# Sheet1.net
KiCad netlist of a schematic drawn in Altium Designer
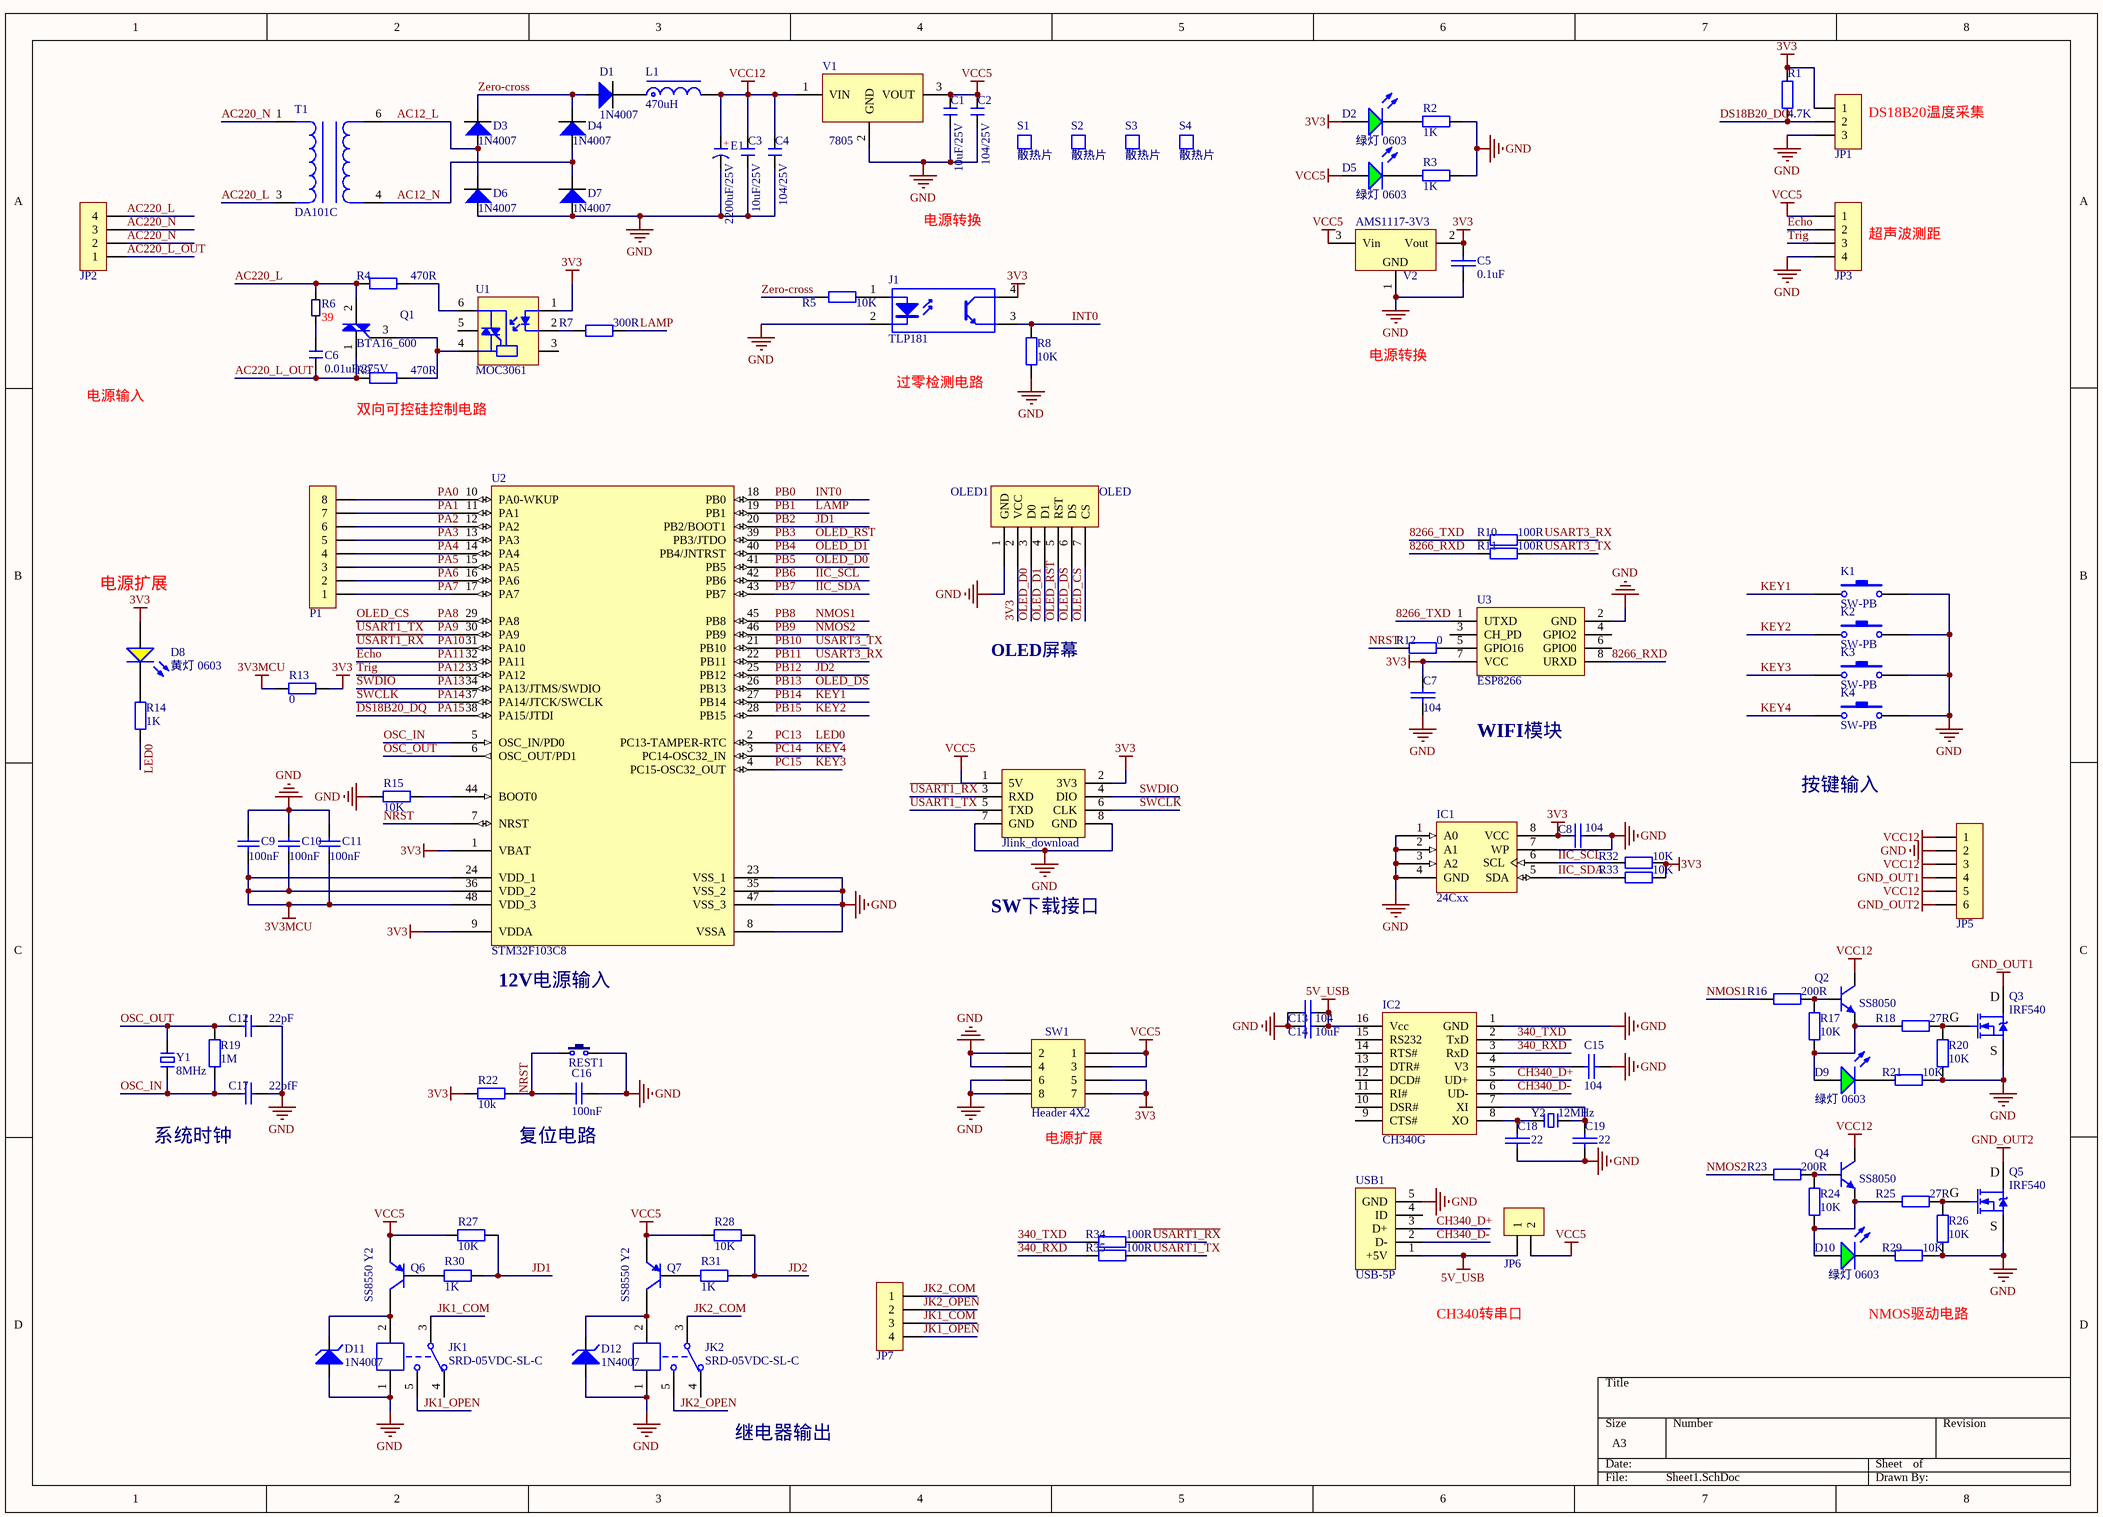
[diagram p0: Sheet1.SchDoc]

(export (version "E")
  (design (tool "Eeschema 10.0.6"))
  (components
    (comp (ref "*1")
      (value "Jlink_download")
      (footprint "HDR2.54-M-LI-2x4P")
      (description "Jlink下载器")
      (libsource (lib "15.1 - 未分类器件") (part "Jlink_下载器"))
    )
    (comp (ref "C1")
      (value "10uF/25V")
      (footprint "LC-0805_C")
      (description "无极性贴片电容")
      (fields (field (name "版权归属") "源创客"))
      (libsource (lib "3.1   - 电阻-电容-电感") (part "C"))
    )
    (comp (ref "C2")
      (value "104/25V")
      (footprint "LC-0603_C")
      (description "无极性贴片电容")
      (fields (field (name "版权归属") "源创客"))
      (libsource (lib "3.1   - 电阻-电容-电感") (part "C"))
    )
    (comp (ref "C3")
      (value "10uF/25V")
      (footprint "LC-0805_C")
      (description "无极性贴片电容")
      (fields (field (name "版权归属") "源创客"))
      (libsource (lib "3.1   - 电阻-电容-电感") (part "C"))
    )
    (comp (ref "C4")
      (value "104/25V")
      (footprint "LC-0603_C")
      (description "无极性贴片电容")
      (fields (field (name "版权归属") "源创客"))
      (libsource (lib "3.1   - 电阻-电容-电感") (part "C"))
    )
    (comp (ref "C5")
      (value "0.1uF")
      (footprint "LC-0603_C")
      (description "Capacitor 0805")
      (libsource (lib "CD's_LIB_2018") (part "0805C"))
    )
    (comp (ref "C6")
      (value "0.01uF/275V")
      (footprint "CBB 10*12*8")
      (description "CBB电容")
      (fields (field (name "版权归属") "源创客"))
      (libsource (lib "3.1   - 电阻-电容-电感") (part "C-CBB"))
    )
    (comp (ref "C7")
      (value "104")
      (footprint "LC-0603_C")
      (description "Capacitor 0805")
      (libsource (lib "CD's_LIB_2018") (part "0805C"))
    )
    (comp (ref "C8")
      (value "104")
      (footprint "LC-0603_C")
      (description "Capacitor 0805")
      (libsource (lib "CD's_LIB_2018") (part "0805C"))
    )
    (comp (ref "C9")
      (value "100nF")
      (footprint "LC-0603_C")
      (description "无极性电容")
      (fields (field (name "PUBLISHER") "Altium Limited"))
      (libsource (lib "liu_2016") (part "Cap"))
    )
    (comp (ref "C10")
      (value "100nF")
      (footprint "LC-0603_C")
      (description "无极性电容")
      (fields (field (name "PUBLISHER") "Altium Limited"))
      (libsource (lib "liu_2016") (part "Cap"))
    )
    (comp (ref "C11")
      (value "100nF")
      (footprint "LC-0603_C")
      (description "无极性电容")
      (fields (field (name "PUBLISHER") "Altium Limited"))
      (libsource (lib "liu_2016") (part "Cap"))
    )
    (comp (ref "C12")
      (value "22pF")
      (footprint "LC-0603_C")
      (description "无极性电容")
      (fields (field (name "PUBLISHER") "Altium Limited"))
      (libsource (lib "liu_2016") (part "Cap"))
    )
    (comp (ref "C13")
      (value "104")
      (footprint "LC-0603_C")
      (description "Capacitor 0805")
      (libsource (lib "CD's_LIB_2018") (part "0805C"))
    )
    (comp (ref "C14")
      (value "10uF")
      (footprint "LC-0805_C")
      (description "Capacitor 0805")
      (libsource (lib "CD's_LIB_2018") (part "0805C"))
    )
    (comp (ref "C15")
      (value "104")
      (footprint "LC-0603_C")
      (description "Capacitor 0805")
      (libsource (lib "CD's_LIB_2018") (part "0805C"))
    )
    (comp (ref "C16")
      (value "100nF")
      (footprint "LC-0603_C")
      (description "无极性电容")
      (fields (field (name "PUBLISHER") "Altium Limited"))
      (libsource (lib "liu_2016") (part "Cap"))
    )
    (comp (ref "C17")
      (value "22pfF")
      (footprint "LC-0603_C")
      (description "无极性电容")
      (fields (field (name "PUBLISHER") "Altium Limited"))
      (libsource (lib "liu_2016") (part "Cap"))
    )
    (comp (ref "C18")
      (value "22")
      (footprint "LC-0603_C")
      (description "Capacitor 0805")
      (libsource (lib "CD's_LIB_2018") (part "0805C"))
    )
    (comp (ref "C19")
      (value "22")
      (footprint "LC-0603_C")
      (description "Capacitor 0805")
      (libsource (lib "CD's_LIB_2018") (part "0805C"))
    )
    (comp (ref "D1") (value "1N4007") (footprint "DO-41") (libsource (lib "SWUST_PanPan") (part "1N4007")))
    (comp (ref "D2")
      (value "绿灯 0603")
      (footprint "LC-0603_LED_S1")
      (description "发光二极管")
      (libsource (lib "Miscellaneous Devices LC") (part "0603 绿灯"))
    )
    (comp (ref "D3") (value "1N4007") (footprint "DO-41") (libsource (lib "SWUST_PanPan") (part "1N4007")))
    (comp (ref "D4") (value "1N4007") (footprint "DO-41") (libsource (lib "SWUST_PanPan") (part "1N4007")))
    (comp (ref "D5")
      (value "绿灯 0603")
      (footprint "LC-0603_LED_S1")
      (description "发光二极管")
      (libsource (lib "Miscellaneous Devices LC") (part "0603 绿灯"))
    )
    (comp (ref "D6") (value "1N4007") (footprint "DO-41") (libsource (lib "SWUST_PanPan") (part "1N4007")))
    (comp (ref "D7") (value "1N4007") (footprint "DO-41") (libsource (lib "SWUST_PanPan") (part "1N4007")))
    (comp (ref "D8")
      (value "黄灯 0603")
      (footprint "LC-0603_LED_S1")
      (description "发光二极管")
      (libsource (lib "Miscellaneous Devices LC") (part "0603 黄灯"))
    )
    (comp (ref "D9")
      (value "绿灯 0603")
      (footprint "LC-0603_LED_S1")
      (description "发光二极管")
      (libsource (lib "Miscellaneous Devices LC") (part "0603 绿灯"))
    )
    (comp (ref "D10")
      (value "绿灯 0603")
      (footprint "LC-0603_LED_S1")
      (description "发光二极管")
      (libsource (lib "Miscellaneous Devices LC") (part "0603 绿灯"))
    )
    (comp (ref "D11")
      (value "1N4007")
      (footprint "D1812")
      (description "Zener Diode")
      (libsource (lib "CD's_LIB_2018") (part "1N4007"))
    )
    (comp (ref "D12")
      (value "1N4007")
      (footprint "D1812")
      (description "Zener Diode")
      (libsource (lib "CD's_LIB_2018") (part "1N4007"))
    )
    (comp (ref "E1")
      (value "2200uF/25V")
      (footprint "CAP 7.5*16*31.5 - BK")
      (description "直插电解电容")
      (fields (field (name "版权归属") "源创客"))
      (libsource (lib "3.1   - 电阻-电容-电感") (part "C-CAP"))
    )
    (comp (ref "IC1")
      (value "24Cxx")
      (footprint "SOP8_M")
      (description "外置EEPROM")
      (fields (field (name "版权归属") "源创客"))
      (libsource (lib "1.1   - IC芯片") (part "24Cxx"))
    )
    (comp (ref "IC2")
      (value "CH340G")
      (footprint "SOP16_M")
      (description "串口转USB")
      (fields (field (name "版权归属") "源创客"))
      (libsource (lib "1.1   - IC芯片") (part "CH340G"))
    )
    (comp (ref "J1")
      (value "TLP181")
      (footprint "SOP4-W2.54_M")
      (description "光耦")
      (fields (field (name "版权归属") "源创客"))
      (libsource (lib "11.1 - 传感元件") (part "TLP181"))
    )
    (comp (ref "JK1")
      (value "SRD-05VDC-SL-C")
      (footprint "SRD-C_B")
      (description "5V一组转换")
      (fields (field (name "版权归属") "源创客"))
      (libsource (lib "7.1   - 继电器") (part "SRD-05VDC-SL-C"))
    )
    (comp (ref "JK2")
      (value "SRD-05VDC-SL-C")
      (footprint "SRD-C_B")
      (description "5V一组转换")
      (fields (field (name "版权归属") "源创客"))
      (libsource (lib "7.1   - 继电器") (part "SRD-05VDC-SL-C"))
    )
    (comp (ref "JP1")
      (value "HDR-1X3")
      (footprint "XH2.54-WI-3P")
      (description "3P接插件")
      (fields (field (name "版权归属") "源创客"))
      (libsource (lib "4.5   - 接插件-脚距2.54") (part "Header 3"))
    )
    (comp (ref "JP2")
      (value "HDR-1X4")
      (footprint "KF128-5.08-4P")
      (description "4P接插件")
      (fields (field (name "版权归属") "源创客"))
      (libsource (lib "4.10 - 接插件-脚距5.08") (part "Header 4"))
    )
    (comp (ref "JP3")
      (value "HDR-1X4")
      (footprint "XH2.54-WI-4P")
      (description "4P接插件")
      (fields (field (name "版权归属") "源创客"))
      (libsource (lib "4.5   - 接插件-脚距2.54") (part "Header 4"))
    )
    (comp (ref "JP5")
      (value "HDR-1X6")
      (footprint "KF128-5.08-6P")
      (description "6P接插件")
      (fields (field (name "版权归属") "源创客"))
      (libsource (lib "4.10 - 接插件-脚距5.08") (part "Header 6"))
    )
    (comp (ref "JP6")
      (value "HDR-1X2")
      (footprint "HDR2.54-LI-2P")
      (description "2P接插件")
      (fields (field (name "版权归属") "源创客"))
      (libsource (lib "4.5   - 接插件-脚距2.54") (part "Header 2"))
    )
    (comp (ref "JP7")
      (value "HDR-1X4")
      (footprint "KF128-5.08-4P")
      (description "4P接插件")
      (fields (field (name "版权归属") "源创客"))
      (libsource (lib "") (part "Header 4_1"))
    )
    (comp (ref "K1")
      (value "SW-PB")
      (footprint "TSW DIP-6*6*5")
      (description "Switch")
      (fields (field (name "PUBLISHER") "Altium Limited"))
      (libsource (lib "PCB_Project") (part "SW-PB"))
    )
    (comp (ref "K2")
      (value "SW-PB")
      (footprint "TSW DIP-6*6*5")
      (description "Switch")
      (fields (field (name "PUBLISHER") "Altium Limited"))
      (libsource (lib "PCB_Project") (part "SW-PB"))
    )
    (comp (ref "K3")
      (value "SW-PB")
      (footprint "TSW DIP-6*6*5")
      (description "Switch")
      (fields (field (name "PUBLISHER") "Altium Limited"))
      (libsource (lib "PCB_Project") (part "SW-PB"))
    )
    (comp (ref "K4")
      (value "SW-PB")
      (footprint "TSW DIP-6*6*5")
      (description "Switch")
      (fields (field (name "PUBLISHER") "Altium Limited"))
      (libsource (lib "PCB_Project") (part "SW-PB"))
    )
    (comp (ref "L1")
      (value "470uH")
      (footprint "LMR135")
      (description "功率磁环电感")
      (fields (field (name "版权归属") "源创客"))
      (libsource (lib "3.1   - 电阻-电容-电感") (part "L-MR"))
    )
    (comp (ref "OLED1")
      (value "OLED")
      (footprint "OLED_096")
      (description "OLED屏幕")
      (libsource (lib "liu_2016") (part "OLED_SPI"))
    )
    (comp (ref "P1")
      (value "HDR-1X8")
      (footprint "HDR2.54-LI-8P")
      (description "8P接插件")
      (fields (field (name "版权归属") "源创客"))
      (libsource (lib "4.5   - 接插件-脚距2.54") (part "Header 8"))
    )
    (comp (ref "Q1")
      (value "BTA16_600")
      (footprint "TO220A")
      (description "双向可控硅")
      (fields (field (name "版权归属") "源创客"))
      (libsource (lib "6.1   - 场效应管-可控硅") (part "BTA12_600"))
    )
    (comp (ref "Q2")
      (value "SS8050")
      (footprint "SOT23-3L")
      (description "高频放大-NPN型")
      (fields (field (name "版权归属") "源创客"))
      (libsource (lib "6.2   - 三极管") (part "8050-SMD"))
    )
    (comp (ref "Q3")
      (value "IRF540")
      (footprint "TO220A")
      (description "N沟场效应管")
      (fields (field (name "版权归属") "源创客"))
      (libsource (lib "6.1   - 场效应管-可控硅") (part "IRF840"))
    )
    (comp (ref "Q4")
      (value "SS8050")
      (footprint "SOT23-3L")
      (description "高频放大-NPN型")
      (fields (field (name "版权归属") "源创客"))
      (libsource (lib "6.2   - 三极管") (part "8050-SMD"))
    )
    (comp (ref "Q5")
      (value "IRF540")
      (footprint "TO220A")
      (description "N沟场效应管")
      (fields (field (name "版权归属") "源创客"))
      (libsource (lib "6.1   - 场效应管-可控硅") (part "IRF840"))
    )
    (comp (ref "Q6")
      (value "SS8550 Y2")
      (footprint "LC-SOT-23(SOT-23-3)")
      (description "三极管")
      (libsource (lib "Miscellaneous Devices LC") (part "SOT-23 SS8550 Y2"))
    )
    (comp (ref "Q7")
      (value "SS8550 Y2")
      (footprint "LC-SOT-23(SOT-23-3)")
      (description "三极管")
      (libsource (lib "Miscellaneous Devices LC") (part "SOT-23 SS8550 Y2"))
    )
    (comp (ref "R1")
      (value "4.7K")
      (footprint "LC-0603_R")
      (description "贴片电阻")
      (fields (field (name "PUBLISHER") "Altium Limited"))
      (libsource (lib "") (part "Res1_1"))
    )
    (comp (ref "R2")
      (value "1K")
      (footprint "LC-0603_R")
      (description "贴片电阻")
      (libsource (lib "Miscellaneous Devices LC") (part "0603 1.1KΩ (1101) 1%"))
    )
    (comp (ref "R3")
      (value "1K")
      (footprint "LC-0603_R")
      (description "贴片电阻")
      (libsource (lib "Miscellaneous Devices LC") (part "0603 1.1KΩ (1101) 1%"))
    )
    (comp (ref "R4")
      (value "470R")
      (footprint "RS 1/2W")
      (description "直插色环电阻")
      (fields (field (name "版权归属") "源创客"))
      (libsource (lib "3.1   - 电阻-电容-电感") (part "R-CRR"))
    )
    (comp (ref "R5")
      (value "10K")
      (footprint "LC-0603_R")
      (description "贴片电阻")
      (fields (field (name "PUBLISHER") "Altium Limited"))
      (libsource (lib "") (part "Res1_2"))
    )
    (comp (ref "R6") (value "39") (footprint "RS 2W") (libsource (lib "SWUST_PanPan") (part "RES-0603")))
    (comp (ref "R7")
      (value "300R")
      (footprint "LC-0603_R")
      (description "贴片电阻")
      (fields (field (name "PUBLISHER") "Altium Limited"))
      (libsource (lib "") (part "Res1_2"))
    )
    (comp (ref "R8")
      (value "10K")
      (footprint "LC-0603_R")
      (description "贴片电阻")
      (fields (field (name "PUBLISHER") "Altium Limited"))
      (libsource (lib "") (part "Res1_3"))
    )
    (comp (ref "R9")
      (value "470R")
      (footprint "RS 1/2W")
      (description "直插色环电阻")
      (fields (field (name "版权归属") "源创客"))
      (libsource (lib "3.1   - 电阻-电容-电感") (part "R-CRR"))
    )
    (comp (ref "R10")
      (value "100R")
      (footprint "LC-0603_R")
      (description "贴片电阻")
      (fields (field (name "PUBLISHER") "Altium Limited"))
      (libsource (lib "liu_2016") (part "Res1"))
    )
    (comp (ref "R11")
      (value "100R")
      (footprint "LC-0603_R")
      (description "贴片电阻")
      (fields (field (name "PUBLISHER") "Altium Limited"))
      (libsource (lib "liu_2016") (part "Res1"))
    )
    (comp (ref "R12")
      (value "0")
      (footprint "LC-0603_R")
      (description "贴片电阻")
      (fields (field (name "PUBLISHER") "Altium Limited"))
      (libsource (lib "liu_2016") (part "Res1"))
    )
    (comp (ref "R13")
      (value "0")
      (footprint "LC-0603_R")
      (description "贴片电阻")
      (fields (field (name "PUBLISHER") "Altium Limited"))
      (libsource (lib "liu_2016") (part "Res1"))
    )
    (comp (ref "R14")
      (value "1K")
      (footprint "LC-0603_R")
      (description "贴片电阻")
      (fields (field (name "PUBLISHER") "Altium Limited"))
      (libsource (lib "") (part "Res1_1"))
    )
    (comp (ref "R15")
      (value "10K")
      (footprint "LC-0603_R")
      (description "贴片电阻")
      (fields (field (name "PUBLISHER") "Altium Limited"))
      (libsource (lib "liu_2016") (part "Res1"))
    )
    (comp (ref "R16")
      (value "200R")
      (footprint "LC-0603_R")
      (description "贴片电阻")
      (fields (field (name "PUBLISHER") "Altium Limited"))
      (libsource (lib "") (part "Res1_1"))
    )
    (comp (ref "R17")
      (value "10K")
      (footprint "LC-0603_R")
      (description "贴片电阻")
      (fields (field (name "PUBLISHER") "Altium Limited"))
      (libsource (lib "毕业设计") (part "Res1"))
    )
    (comp (ref "R18")
      (value "27R")
      (footprint "LC-0603_R")
      (description "贴片电阻")
      (fields (field (name "PUBLISHER") "Altium Limited"))
      (libsource (lib "") (part "Res1_1"))
    )
    (comp (ref "R19")
      (value "1M")
      (footprint "LC-0603_R")
      (description "贴片电阻")
      (fields (field (name "PUBLISHER") "Altium Limited"))
      (libsource (lib "") (part "Res1_2"))
    )
    (comp (ref "R20")
      (value "10K")
      (footprint "LC-0603_R")
      (description "贴片电阻")
      (fields (field (name "PUBLISHER") "Altium Limited"))
      (libsource (lib "毕业设计") (part "Res1"))
    )
    (comp (ref "R21")
      (value "10K")
      (footprint "LC-0603_R")
      (description "贴片电阻")
      (libsource (lib "Miscellaneous Devices LC") (part "0603 1.1KΩ (1101) 1%"))
    )
    (comp (ref "R22")
      (value "10k")
      (footprint "LC-0603_R")
      (description "贴片电阻")
      (fields (field (name "PUBLISHER") "Altium Limited"))
      (libsource (lib "") (part "Res1_3"))
    )
    (comp (ref "R23")
      (value "200R")
      (footprint "LC-0603_R")
      (description "贴片电阻")
      (fields (field (name "PUBLISHER") "Altium Limited"))
      (libsource (lib "") (part "Res1_1"))
    )
    (comp (ref "R24")
      (value "10K")
      (footprint "LC-0603_R")
      (description "贴片电阻")
      (fields (field (name "PUBLISHER") "Altium Limited"))
      (libsource (lib "毕业设计") (part "Res1"))
    )
    (comp (ref "R25")
      (value "27R")
      (footprint "LC-0603_R")
      (description "贴片电阻")
      (fields (field (name "PUBLISHER") "Altium Limited"))
      (libsource (lib "") (part "Res1_1"))
    )
    (comp (ref "R26")
      (value "10K")
      (footprint "LC-0603_R")
      (description "贴片电阻")
      (fields (field (name "PUBLISHER") "Altium Limited"))
      (libsource (lib "毕业设计") (part "Res1"))
    )
    (comp (ref "R27")
      (value "10K")
      (footprint "LC-0603_R")
      (description "贴片电阻")
      (libsource (lib "Miscellaneous Devices LC") (part "0603 1.1KΩ (1101) 1%"))
    )
    (comp (ref "R28")
      (value "10K")
      (footprint "LC-0603_R")
      (description "贴片电阻")
      (libsource (lib "Miscellaneous Devices LC") (part "0603 1.1KΩ (1101) 1%"))
    )
    (comp (ref "R29")
      (value "10K")
      (footprint "LC-0603_R")
      (description "贴片电阻")
      (libsource (lib "Miscellaneous Devices LC") (part "0603 1.1KΩ (1101) 1%"))
    )
    (comp (ref "R30")
      (value "1K")
      (footprint "LC-0603_R")
      (description "贴片电阻")
      (libsource (lib "Miscellaneous Devices LC") (part "0603 1.1KΩ (1101) 1%"))
    )
    (comp (ref "R31")
      (value "1K")
      (footprint "LC-0603_R")
      (description "贴片电阻")
      (libsource (lib "Miscellaneous Devices LC") (part "0603 1.1KΩ (1101) 1%"))
    )
    (comp (ref "R32")
      (value "10K")
      (footprint "LC-0603_R")
      (description "贴片电阻")
      (libsource (lib "Miscellaneous Devices LC") (part "0603 1.1KΩ (1101) 1%"))
    )
    (comp (ref "R33")
      (value "10K")
      (footprint "LC-0603_R")
      (description "贴片电阻")
      (libsource (lib "Miscellaneous Devices LC") (part "0603 1.1KΩ (1101) 1%"))
    )
    (comp (ref "R34")
      (value "100R")
      (footprint "LC-0603_R")
      (description "贴片电阻")
      (fields (field (name "PUBLISHER") "Altium Limited"))
      (libsource (lib "liu_2016") (part "Res1"))
    )
    (comp (ref "R35")
      (value "100R")
      (footprint "LC-0603_R")
      (description "贴片电阻")
      (fields (field (name "PUBLISHER") "Altium Limited"))
      (libsource (lib "liu_2016") (part "Res1"))
    )
    (comp (ref "REST1")
      (value "3x6x5")
      (footprint "TSW SMD-3*6*2.5")
      (description "3x6轻触开关")
      (fields (field (name "版权归属") "源创客"))
      (libsource (lib "5.1   - 按键-开关") (part "TSW 3x6"))
    )
    (comp (ref "S1")
      (value "散热片")
      (footprint "SRP10-15-21-P")
      (fields (field (name "版权归属") "源创客"))
      (libsource (lib "15.1 - 未分类器件") (part "S1"))
    )
    (comp (ref "S2")
      (value "散热片")
      (footprint "SRP10-15-21-P")
      (fields (field (name "版权归属") "源创客"))
      (libsource (lib "15.1 - 未分类器件") (part "S1"))
    )
    (comp (ref "S3")
      (value "散热片")
      (footprint "SRP10-15-21-P")
      (fields (field (name "版权归属") "源创客"))
      (libsource (lib "15.1 - 未分类器件") (part "S1"))
    )
    (comp (ref "S4")
      (value "散热片")
      (footprint "SRP10-15-21-P")
      (fields (field (name "版权归属") "源创客"))
      (libsource (lib "15.1 - 未分类器件") (part "S1"))
    )
    (comp (ref "SW1")
      (value "Header 4X2")
      (footprint "HDR2.54-LI-2x4P")
      (description "Header, 4-Pin, Dual row")
      (fields (field (name "PUBLISHER") "Altium Limited"))
      (libsource (lib "Sparks") (part "Header 4X2"))
    )
    (comp (ref "T1")
      (value "DA101C")
      (footprint "Transformer_28mm")
      (description "数字隔离变压器")
      (fields (field (name "版权归属") "源创客"))
      (libsource (lib "12.1 - 变压器") (part "DA10XC"))
    )
    (comp (ref "U1")
      (value "MOC3061")
      (footprint "DIP6-300")
      (description "零点触发光可控硅")
      (fields (field (name "版权归属") "源创客"))
      (libsource (lib "6.1   - 场效应管-可控硅") (part "MOC3061"))
    )
    (comp (ref "U2")
      (value "STM32F103C8")
      (footprint "LQFP48 7X7_M")
      (description "Flaah:64/RAM:20/IO:36")
      (fields (field (name "版权归属") "源创客"))
      (libsource (lib "2.1   - STM32系列单片机") (part "STM32F103C8"))
    )
    (comp (ref "U3")
      (value "ESP8266")
      (footprint "2*4HEADER")
      (description "WIFI通信模块")
      (libsource (lib "13.1 - 模块") (part "ESP8266"))
    )
    (comp (ref "USB1")
      (value "USB-5P")
      (footprint "USB-MICRO_A")
      (description "微型USB母座")
      (fields (field (name "版权归属") "源创客"))
      (libsource (lib "4.1   - 接口类") (part "USB-5P"))
    )
    (comp (ref "V1")
      (value "7805")
      (footprint "TO220A")
      (description "线性稳压芯片")
      (fields (field (name "版权归属") "源创客"))
      (libsource (lib "1.3   - 电源类芯片") (part "78xx"))
    )
    (comp (ref "V2")
      (value "AMS1117-3V3")
      (footprint "SOT223_N")
      (description "三端稳压芯片")
      (fields (field (name "版权归属") "源创客"))
      (libsource (lib "1.3   - 电源类芯片") (part "AMS1117"))
    )
    (comp (ref "Y1")
      (value "8MHz")
      (footprint "OSC HC-49S")
      (description "2脚无源脚晶振")
      (fields (field (name "版权归属") "源创客"))
      (libsource (lib "10.1 - 保险丝-晶振") (part "XTAL-2P"))
    )
    (comp (ref "Y2")
      (value "12MHz")
      (footprint "OSC HC-49S")
      (description "2脚无源脚晶振")
      (fields (field (name "版权归属") "源创客"))
      (libsource (lib "10.1 - 保险丝-晶振") (part "XTAL-2P"))
    )
  )
  (nets
    (net (code "1") (name "/340_RXD") (class "Default")
      (node (ref "IC2") (pin "3") (pinfunction "RxD_3") (pintype "passive"))
      (node (ref "R35") (pin "2") (pinfunction "2_2") (pintype "passive"))
    )
    (net (code "2") (name "/340_TXD") (class "Default")
      (node (ref "IC2") (pin "2") (pinfunction "TxD_2") (pintype "passive"))
      (node (ref "R34") (pin "2") (pinfunction "2_2") (pintype "passive"))
    )
    (net (code "3") (name "/8266_RXD") (class "Default")
      (node (ref "R11") (pin "2") (pinfunction "2_2") (pintype "passive"))
      (node (ref "U3") (pin "8") (pinfunction "URXD_8") (pintype "passive"))
    )
    (net (code "4") (name "/8266_TXD") (class "Default")
      (node (ref "R10") (pin "2") (pinfunction "2_2") (pintype "passive"))
      (node (ref "U3") (pin "1") (pinfunction "UTXD_1") (pintype "passive"))
    )
    (net (code "5") (name "/AC12_L") (class "Default")
      (node (ref "D3") (pin "1") (pinfunction "1_1") (pintype "passive"))
      (node (ref "D6") (pin "2") (pinfunction "2_2") (pintype "passive"))
      (node (ref "T1") (pin "6") (pinfunction "6_6") (pintype "passive"))
    )
    (net (code "6") (name "/AC12_N") (class "Default")
      (node (ref "D4") (pin "1") (pinfunction "1_1") (pintype "passive"))
      (node (ref "D7") (pin "2") (pinfunction "2_2") (pintype "passive"))
      (node (ref "T1") (pin "4") (pinfunction "4_4") (pintype "passive"))
    )
    (net (code "7") (name "/AC220_L") (class "Default")
      (node (ref "JP2") (pin "4") (pinfunction "4_4") (pintype "passive"))
      (node (ref "Q1") (pin "2") (pinfunction "A2_2") (pintype "passive"))
      (node (ref "R4") (pin "1") (pinfunction "1_1") (pintype "passive"))
      (node (ref "R6") (pin "2") (pinfunction "2_2") (pintype "passive"))
      (node (ref "T1") (pin "3") (pinfunction "3_3") (pintype "passive"))
    )
    (net (code "8") (name "/AC220_L_OUT") (class "Default")
      (node (ref "C6") (pin "1") (pinfunction "1_1") (pintype "passive"))
      (node (ref "JP2") (pin "1") (pinfunction "1_1") (pintype "passive"))
      (node (ref "Q1") (pin "1") (pinfunction "A1_1") (pintype "passive"))
      (node (ref "R9") (pin "1") (pinfunction "1_1") (pintype "passive"))
    )
    (net (code "9") (name "/AC220_N") (class "Default")
      (node (ref "JP2") (pin "2") (pinfunction "2_2") (pintype "passive"))
      (node (ref "JP2") (pin "3") (pinfunction "3_3") (pintype "passive"))
      (node (ref "T1") (pin "1") (pinfunction "1_1") (pintype "passive"))
    )
    (net (code "10") (name "/CH340_D+") (class "Default")
      (node (ref "IC2") (pin "5") (pinfunction "UD+_5") (pintype "passive"))
      (node (ref "USB1") (pin "3") (pinfunction "D+_3") (pintype "passive"))
    )
    (net (code "11") (name "/CH340_D-") (class "Default")
      (node (ref "IC2") (pin "6") (pinfunction "UD-_6") (pintype "passive"))
      (node (ref "USB1") (pin "2") (pinfunction "D-_2") (pintype "passive"))
    )
    (net (code "12") (name "/DS18B20_DQ") (class "Default")
      (node (ref "JP1") (pin "2") (pinfunction "2_2") (pintype "passive"))
      (node (ref "R1") (pin "2") (pinfunction "2_2") (pintype "passive"))
      (node (ref "U2") (pin "38") (pinfunction "PA15/JTDI_38") (pintype "bidirectional"))
    )
    (net (code "13") (name "/Echo") (class "Default")
      (node (ref "JP3") (pin "2") (pinfunction "2_2") (pintype "passive"))
      (node (ref "U2") (pin "32") (pinfunction "PA11_32") (pintype "bidirectional"))
    )
    (net (code "14") (name "/IIC_SCL") (class "Default")
      (node (ref "IC1") (pin "6") (pinfunction "SCL_6") (pintype "input"))
      (node (ref "R32") (pin "2") (pinfunction "2_2") (pintype "passive"))
      (node (ref "U2") (pin "42") (pinfunction "PB6_42") (pintype "bidirectional"))
    )
    (net (code "15") (name "/IIC_SDA") (class "Default")
      (node (ref "IC1") (pin "5") (pinfunction "SDA_5") (pintype "bidirectional"))
      (node (ref "R33") (pin "2") (pinfunction "2_2") (pintype "passive"))
      (node (ref "U2") (pin "43") (pinfunction "PB7_43") (pintype "bidirectional"))
    )
    (net (code "16") (name "/INT0") (class "Default")
      (node (ref "J1") (pin "3") (pinfunction "E_3") (pintype "passive"))
      (node (ref "R8") (pin "2") (pinfunction "2_2") (pintype "passive"))
      (node (ref "U2") (pin "18") (pinfunction "PB0_18") (pintype "bidirectional"))
    )
    (net (code "17") (name "/JD1") (class "Default")
      (node (ref "R27") (pin "1") (pinfunction "1_1") (pintype "passive"))
      (node (ref "R30") (pin "1") (pinfunction "1_1") (pintype "passive"))
      (node (ref "U2") (pin "20") (pinfunction "PB2/BOOT1_20") (pintype "bidirectional"))
    )
    (net (code "18") (name "/JD2") (class "Default")
      (node (ref "R28") (pin "1") (pinfunction "1_1") (pintype "passive"))
      (node (ref "R31") (pin "1") (pinfunction "1_1") (pintype "passive"))
      (node (ref "U2") (pin "25") (pinfunction "PB12_25") (pintype "bidirectional"))
    )
    (net (code "19") (name "/JK1_COM") (class "Default")
      (node (ref "JK1") (pin "3") (pinfunction "3_3") (pintype "passive"))
      (node (ref "JP7") (pin "3") (pinfunction "3_3") (pintype "passive"))
    )
    (net (code "20") (name "/JK1_OPEN") (class "Default")
      (node (ref "JK1") (pin "5") (pinfunction "5_5") (pintype "passive"))
      (node (ref "JP7") (pin "4") (pinfunction "4_4") (pintype "passive"))
    )
    (net (code "21") (name "/JK2_COM") (class "Default")
      (node (ref "JK2") (pin "3") (pinfunction "3_3") (pintype "passive"))
      (node (ref "JP7") (pin "1") (pinfunction "1_1") (pintype "passive"))
    )
    (net (code "22") (name "/JK2_OPEN") (class "Default")
      (node (ref "JK2") (pin "5") (pinfunction "5_5") (pintype "passive"))
      (node (ref "JP7") (pin "2") (pinfunction "2_2") (pintype "passive"))
    )
    (net (code "23") (name "/KEY1") (class "Default")
      (node (ref "K1") (pin "1") (pinfunction "1_1") (pintype "passive"))
      (node (ref "U2") (pin "27") (pinfunction "PB14_27") (pintype "bidirectional"))
    )
    (net (code "24") (name "/KEY2") (class "Default")
      (node (ref "K2") (pin "1") (pinfunction "1_1") (pintype "passive"))
      (node (ref "U2") (pin "28") (pinfunction "PB15_28") (pintype "bidirectional"))
    )
    (net (code "25") (name "/KEY3") (class "Default")
      (node (ref "K3") (pin "1") (pinfunction "1_1") (pintype "passive"))
      (node (ref "U2") (pin "4") (pinfunction "PC15-OSC32_OUT_4") (pintype "bidirectional"))
    )
    (net (code "26") (name "/KEY4") (class "Default")
      (node (ref "K4") (pin "1") (pinfunction "1_1") (pintype "passive"))
      (node (ref "U2") (pin "3") (pinfunction "PC14-OSC32_IN_3") (pintype "bidirectional"))
    )
    (net (code "27") (name "/LAMP") (class "Default")
      (node (ref "R7") (pin "2") (pinfunction "2_2") (pintype "passive"))
      (node (ref "U2") (pin "19") (pinfunction "PB1_19") (pintype "bidirectional"))
    )
    (net (code "28") (name "/LED0") (class "Default")
      (node (ref "R14") (pin "2") (pinfunction "2_2") (pintype "passive"))
      (node (ref "U2") (pin "2") (pinfunction "PC13-TAMPER-RTC_2") (pintype "bidirectional"))
    )
    (net (code "29") (name "/NMOS1") (class "Default")
      (node (ref "R16") (pin "2") (pinfunction "2_2") (pintype "passive"))
      (node (ref "U2") (pin "45") (pinfunction "PB8_45") (pintype "bidirectional"))
    )
    (net (code "30") (name "/NMOS2") (class "Default")
      (node (ref "R23") (pin "2") (pinfunction "2_2") (pintype "passive"))
      (node (ref "U2") (pin "46") (pinfunction "PB9_46") (pintype "bidirectional"))
    )
    (net (code "31") (name "/NRST") (class "Default")
      (node (ref "C16") (pin "1") (pinfunction "1_1") (pintype "passive"))
      (node (ref "R12") (pin "2") (pinfunction "2_2") (pintype "passive"))
      (node (ref "R22") (pin "2") (pinfunction "2_2") (pintype "passive"))
      (node (ref "REST1") (pin "1") (pinfunction "1_1") (pintype "passive"))
      (node (ref "U2") (pin "7") (pinfunction "NRST_7") (pintype "bidirectional"))
    )
    (net (code "32") (name "/OLED_CS") (class "Default")
      (node (ref "OLED1") (pin "7") (pinfunction "CS_7") (pintype "passive"))
      (node (ref "U2") (pin "29") (pinfunction "PA8_29") (pintype "bidirectional"))
    )
    (net (code "33") (name "/OLED_D0") (class "Default")
      (node (ref "OLED1") (pin "3") (pinfunction "D0_3") (pintype "passive"))
      (node (ref "U2") (pin "41") (pinfunction "PB5_41") (pintype "bidirectional"))
    )
    (net (code "34") (name "/OLED_D1") (class "Default")
      (node (ref "OLED1") (pin "4") (pinfunction "D1_4") (pintype "passive"))
      (node (ref "U2") (pin "40") (pinfunction "PB4/JNTRST_40") (pintype "bidirectional"))
    )
    (net (code "35") (name "/OLED_DS") (class "Default")
      (node (ref "OLED1") (pin "6") (pinfunction "DS_6") (pintype "passive"))
      (node (ref "U2") (pin "26") (pinfunction "PB13_26") (pintype "bidirectional"))
    )
    (net (code "36") (name "/OLED_RST") (class "Default")
      (node (ref "OLED1") (pin "5") (pinfunction "RST_5") (pintype "passive"))
      (node (ref "U2") (pin "39") (pinfunction "PB3/JTDO_39") (pintype "bidirectional"))
    )
    (net (code "37") (name "/OSC_IN") (class "Default")
      (node (ref "C17") (pin "1") (pinfunction "1_1") (pintype "passive"))
      (node (ref "R19") (pin "1") (pinfunction "1_1") (pintype "passive"))
      (node (ref "U2") (pin "5") (pinfunction "OSC_IN/PD0_5") (pintype "input"))
      (node (ref "Y1") (pin "1") (pinfunction "1_1") (pintype "passive"))
    )
    (net (code "38") (name "/OSC_OUT") (class "Default")
      (node (ref "C12") (pin "1") (pinfunction "1_1") (pintype "passive"))
      (node (ref "R19") (pin "2") (pinfunction "2_2") (pintype "passive"))
      (node (ref "U2") (pin "6") (pinfunction "OSC_OUT/PD1_6") (pintype "output"))
      (node (ref "Y1") (pin "2") (pinfunction "2_2") (pintype "passive"))
    )
    (net (code "39") (name "/PA0") (class "Default")
      (node (ref "P1") (pin "8") (pinfunction "8_8") (pintype "passive"))
      (node (ref "U2") (pin "10") (pinfunction "PA0-WKUP_10") (pintype "bidirectional"))
    )
    (net (code "40") (name "/PA1") (class "Default")
      (node (ref "P1") (pin "7") (pinfunction "7_7") (pintype "passive"))
      (node (ref "U2") (pin "11") (pinfunction "PA1_11") (pintype "bidirectional"))
    )
    (net (code "41") (name "/PA2") (class "Default")
      (node (ref "P1") (pin "6") (pinfunction "6_6") (pintype "passive"))
      (node (ref "U2") (pin "12") (pinfunction "PA2_12") (pintype "bidirectional"))
    )
    (net (code "42") (name "/PA3") (class "Default")
      (node (ref "P1") (pin "5") (pinfunction "5_5") (pintype "passive"))
      (node (ref "U2") (pin "13") (pinfunction "PA3_13") (pintype "bidirectional"))
    )
    (net (code "43") (name "/PA4") (class "Default")
      (node (ref "P1") (pin "4") (pinfunction "4_4") (pintype "passive"))
      (node (ref "U2") (pin "14") (pinfunction "PA4_14") (pintype "bidirectional"))
    )
    (net (code "44") (name "/PA5") (class "Default")
      (node (ref "P1") (pin "3") (pinfunction "3_3") (pintype "passive"))
      (node (ref "U2") (pin "15") (pinfunction "PA5_15") (pintype "bidirectional"))
    )
    (net (code "45") (name "/PA6") (class "Default")
      (node (ref "P1") (pin "2") (pinfunction "2_2") (pintype "passive"))
      (node (ref "U2") (pin "16") (pinfunction "PA6_16") (pintype "bidirectional"))
    )
    (net (code "46") (name "/PA7") (class "Default")
      (node (ref "P1") (pin "1") (pinfunction "1_1") (pintype "passive"))
      (node (ref "U2") (pin "17") (pinfunction "PA7_17") (pintype "bidirectional"))
    )
    (net (code "47") (name "/PA9") (class "Default")
      (node (ref "*1") (pin "5") (pinfunction "TXD_5") (pintype "passive"))
      (node (ref "R35") (pin "1") (pinfunction "1_1") (pintype "passive"))
      (node (ref "U2") (pin "30") (pinfunction "PA9_30") (pintype "bidirectional"))
    )
    (net (code "48") (name "/PA10") (class "Default")
      (node (ref "*1") (pin "3") (pinfunction "RXD_3") (pintype "passive"))
      (node (ref "R34") (pin "1") (pinfunction "1_1") (pintype "passive"))
      (node (ref "U2") (pin "31") (pinfunction "PA10_31") (pintype "bidirectional"))
    )
    (net (code "49") (name "/PA12") (class "Default")
      (node (ref "JP3") (pin "3") (pinfunction "3_3") (pintype "passive"))
      (node (ref "U2") (pin "33") (pinfunction "PA12_33") (pintype "bidirectional"))
    )
    (net (code "50") (name "/PA13") (class "Default")
      (node (ref "*1") (pin "4") (pinfunction "DIO_4") (pintype "passive"))
      (node (ref "U2") (pin "34") (pinfunction "PA13/JTMS/SWDIO_34") (pintype "bidirectional"))
    )
    (net (code "51") (name "/PA14") (class "Default")
      (node (ref "*1") (pin "6") (pinfunction "CLK_6") (pintype "passive"))
      (node (ref "U2") (pin "37") (pinfunction "PA14/JTCK/SWCLK_37") (pintype "bidirectional"))
    )
    (net (code "52") (name "/PB10") (class "Default")
      (node (ref "R11") (pin "1") (pinfunction "1_1") (pintype "passive"))
      (node (ref "U2") (pin "21") (pinfunction "PB10_21") (pintype "bidirectional"))
    )
    (net (code "53") (name "/PB11") (class "Default")
      (node (ref "R10") (pin "1") (pinfunction "1_1") (pintype "passive"))
      (node (ref "U2") (pin "22") (pinfunction "PB11_22") (pintype "bidirectional"))
    )
    (net (code "54") (name "/Zero-cross") (class "Default")
      (node (ref "D1") (pin "1") (pinfunction "1_1") (pintype "passive"))
      (node (ref "D3") (pin "2") (pinfunction "2_2") (pintype "passive"))
      (node (ref "D4") (pin "2") (pinfunction "2_2") (pintype "passive"))
      (node (ref "R5") (pin "1") (pinfunction "1_1") (pintype "passive"))
    )
    (net (code "55") (name "3V3") (class "Default")
      (node (ref "*1") (pin "2") (pinfunction "3V3_2") (pintype "passive"))
      (node (ref "C5") (pin "2") (pinfunction "2_2") (pintype "passive"))
      (node (ref "C7") (pin "2") (pinfunction "2_2") (pintype "passive"))
      (node (ref "C8") (pin "2") (pinfunction "2_2") (pintype "passive"))
      (node (ref "D2") (pin "A") (pinfunction "A_A") (pintype "passive"))
      (node (ref "D8") (pin "A") (pinfunction "A_A") (pintype "passive"))
      (node (ref "IC1") (pin "8") (pinfunction "VCC_8") (pintype "power_in"))
      (node (ref "J1") (pin "4") (pinfunction "C_4") (pintype "passive"))
      (node (ref "JP1") (pin "1") (pinfunction "1_1") (pintype "passive"))
      (node (ref "OLED1") (pin "2") (pinfunction "VCC_2") (pintype "passive"))
      (node (ref "R1") (pin "1") (pinfunction "1_1") (pintype "passive"))
      (node (ref "R13") (pin "1") (pinfunction "1_1") (pintype "passive"))
      (node (ref "R22") (pin "1") (pinfunction "1_1") (pintype "passive"))
      (node (ref "R32") (pin "1") (pinfunction "1_1") (pintype "passive"))
      (node (ref "R33") (pin "1") (pinfunction "1_1") (pintype "passive"))
      (node (ref "SW1") (pin "5") (pinfunction "5_5") (pintype "passive"))
      (node (ref "SW1") (pin "7") (pinfunction "7_7") (pintype "passive"))
      (node (ref "U1") (pin "1") (pinfunction "+_1") (pintype "passive"))
      (node (ref "U2") (pin "1") (pinfunction "VBAT_1") (pintype "power_in"))
      (node (ref "U2") (pin "9") (pinfunction "VDDA_9") (pintype "power_in"))
      (node (ref "U3") (pin "7") (pinfunction "VCC_7") (pintype "passive"))
      (node (ref "V2") (pin "2") (pinfunction "Vout_2") (pintype "passive"))
    )
    (net (code "56") (name "3V3MCU") (class "Default")
      (node (ref "C10") (pin "1") (pinfunction "1_1") (pintype "passive"))
      (node (ref "C11") (pin "1") (pinfunction "1_1") (pintype "passive"))
      (node (ref "C9") (pin "1") (pinfunction "1_1") (pintype "passive"))
      (node (ref "R13") (pin "2") (pinfunction "2_2") (pintype "passive"))
      (node (ref "U2") (pin "24") (pinfunction "VDD_1_24") (pintype "power_in"))
      (node (ref "U2") (pin "36") (pinfunction "VDD_2_36") (pintype "power_in"))
      (node (ref "U2") (pin "48") (pinfunction "VDD_3_48") (pintype "power_in"))
    )
    (net (code "57") (name "5V_USB") (class "Default")
      (node (ref "C13") (pin "1") (pinfunction "1_1") (pintype "passive"))
      (node (ref "C14") (pin "1") (pinfunction "1_1") (pintype "passive"))
      (node (ref "IC2") (pin "16") (pinfunction "Vcc_16") (pintype "passive"))
      (node (ref "JP6") (pin "1") (pinfunction "1_1") (pintype "passive"))
      (node (ref "USB1") (pin "1") (pinfunction "+5V_1") (pintype "passive"))
    )
    (net (code "58") (name "GND") (class "Default")
      (node (ref "*1") (pin "7") (pinfunction "GND_7") (pintype "passive"))
      (node (ref "*1") (pin "8") (pinfunction "GND_8") (pintype "passive"))
      (node (ref "C1") (pin "1") (pinfunction "1_1") (pintype "passive"))
      (node (ref "C10") (pin "2") (pinfunction "2_2") (pintype "passive"))
      (node (ref "C11") (pin "2") (pinfunction "2_2") (pintype "passive"))
      (node (ref "C12") (pin "2") (pinfunction "2_2") (pintype "passive"))
      (node (ref "C13") (pin "2") (pinfunction "2_2") (pintype "passive"))
      (node (ref "C14") (pin "2") (pinfunction "2_2") (pintype "passive"))
      (node (ref "C15") (pin "1") (pinfunction "1_1") (pintype "passive"))
      (node (ref "C16") (pin "2") (pinfunction "2_2") (pintype "passive"))
      (node (ref "C17") (pin "2") (pinfunction "2_2") (pintype "passive"))
      (node (ref "C18") (pin "2") (pinfunction "2_2") (pintype "passive"))
      (node (ref "C19") (pin "2") (pinfunction "2_2") (pintype "passive"))
      (node (ref "C2") (pin "1") (pinfunction "1_1") (pintype "passive"))
      (node (ref "C3") (pin "1") (pinfunction "1_1") (pintype "passive"))
      (node (ref "C4") (pin "1") (pinfunction "1_1") (pintype "passive"))
      (node (ref "C5") (pin "1") (pinfunction "1_1") (pintype "passive"))
      (node (ref "C7") (pin "1") (pinfunction "1_1") (pintype "passive"))
      (node (ref "C8") (pin "1") (pinfunction "1_1") (pintype "passive"))
      (node (ref "C9") (pin "2") (pinfunction "2_2") (pintype "passive"))
      (node (ref "D11") (pin "1") (pinfunction "A_1") (pintype "passive"))
      (node (ref "D12") (pin "1") (pinfunction "A_1") (pintype "passive"))
      (node (ref "D6") (pin "1") (pinfunction "1_1") (pintype "passive"))
      (node (ref "D7") (pin "1") (pinfunction "1_1") (pintype "passive"))
      (node (ref "E1") (pin "2") (pinfunction "K_2") (pintype "passive"))
      (node (ref "IC1") (pin "1") (pinfunction "A0_1") (pintype "input"))
      (node (ref "IC1") (pin "2") (pinfunction "A1_2") (pintype "input"))
      (node (ref "IC1") (pin "3") (pinfunction "A2_3") (pintype "input"))
      (node (ref "IC1") (pin "4") (pinfunction "GND_4") (pintype "passive"))
      (node (ref "IC1") (pin "7") (pinfunction "WP_7") (pintype "passive"))
      (node (ref "IC2") (pin "1") (pinfunction "GND_1") (pintype "passive"))
      (node (ref "J1") (pin "2") (pinfunction "K_2") (pintype "passive"))
      (node (ref "JK1") (pin "1") (pinfunction "1_1") (pintype "passive"))
      (node (ref "JK2") (pin "1") (pinfunction "1_1") (pintype "passive"))
      (node (ref "JP1") (pin "3") (pinfunction "3_3") (pintype "passive"))
      (node (ref "JP3") (pin "4") (pinfunction "4_4") (pintype "passive"))
      (node (ref "JP5") (pin "2") (pinfunction "2_2") (pintype "passive"))
      (node (ref "K1") (pin "2") (pinfunction "2_2") (pintype "passive"))
      (node (ref "K2") (pin "2") (pinfunction "2_2") (pintype "passive"))
      (node (ref "K3") (pin "2") (pinfunction "2_2") (pintype "passive"))
      (node (ref "K4") (pin "2") (pinfunction "2_2") (pintype "passive"))
      (node (ref "OLED1") (pin "1") (pinfunction "GND_1") (pintype "passive"))
      (node (ref "Q3") (pin "3") (pinfunction "S_3") (pintype "passive"))
      (node (ref "Q5") (pin "3") (pinfunction "S_3") (pintype "passive"))
      (node (ref "R15") (pin "2") (pinfunction "2_2") (pintype "passive"))
      (node (ref "R2") (pin "1") (pinfunction "1_1") (pintype "passive"))
      (node (ref "R20") (pin "2") (pinfunction "2_2") (pintype "passive"))
      (node (ref "R21") (pin "1") (pinfunction "1_1") (pintype "passive"))
      (node (ref "R26") (pin "2") (pinfunction "2_2") (pintype "passive"))
      (node (ref "R29") (pin "1") (pinfunction "1_1") (pintype "passive"))
      (node (ref "R3") (pin "1") (pinfunction "1_1") (pintype "passive"))
      (node (ref "R8") (pin "1") (pinfunction "1_1") (pintype "passive"))
      (node (ref "REST1") (pin "2") (pinfunction "2_2") (pintype "passive"))
      (node (ref "SW1") (pin "2") (pinfunction "2_2") (pintype "passive"))
      (node (ref "SW1") (pin "4") (pinfunction "4_4") (pintype "passive"))
      (node (ref "SW1") (pin "6") (pinfunction "6_6") (pintype "passive"))
      (node (ref "SW1") (pin "8") (pinfunction "8_8") (pintype "passive"))
      (node (ref "U2") (pin "23") (pinfunction "VSS_1_23") (pintype "power_in"))
      (node (ref "U2") (pin "35") (pinfunction "VSS_2_35") (pintype "power_in"))
      (node (ref "U2") (pin "47") (pinfunction "VSS_3_47") (pintype "power_in"))
      (node (ref "U2") (pin "8") (pinfunction "VSSA_8") (pintype "power_in"))
      (node (ref "U3") (pin "2") (pinfunction "GND_2") (pintype "passive"))
      (node (ref "USB1") (pin "5") (pinfunction "GND_5") (pintype "passive"))
      (node (ref "V1") (pin "2") (pinfunction "GND_2") (pintype "passive"))
      (node (ref "V2") (pin "1") (pinfunction "GND_1") (pintype "passive"))
    )
    (net (code "59") (name "GND_OUT1") (class "Default")
      (node (ref "JP5") (pin "4") (pinfunction "4_4") (pintype "passive"))
      (node (ref "Q3") (pin "2") (pinfunction "D_2") (pintype "passive"))
    )
    (net (code "60") (name "GND_OUT2") (class "Default")
      (node (ref "JP5") (pin "6") (pinfunction "6_6") (pintype "passive"))
      (node (ref "Q5") (pin "2") (pinfunction "D_2") (pintype "passive"))
    )
    (net (code "61") (name "Net-(C6-Pad2)") (class "Default")
      (node (ref "C6") (pin "2") (pinfunction "2_2") (pintype "passive"))
      (node (ref "R6") (pin "1") (pinfunction "1_1") (pintype "passive"))
    )
    (net (code "62") (name "Net-(D1-Pad2)") (class "Default")
      (node (ref "D1") (pin "2") (pinfunction "2_2") (pintype "passive"))
      (node (ref "L1") (pin "1") (pinfunction "1_1") (pintype "passive"))
    )
    (net (code "63") (name "Net-(D2-PadK)") (class "Default")
      (node (ref "D2") (pin "K") (pinfunction "K_K") (pintype "passive"))
      (node (ref "R2") (pin "2") (pinfunction "2_2") (pintype "passive"))
    )
    (net (code "64") (name "Net-(D5-PadK)") (class "Default")
      (node (ref "D5") (pin "K") (pinfunction "K_K") (pintype "passive"))
      (node (ref "R3") (pin "2") (pinfunction "2_2") (pintype "passive"))
    )
    (net (code "65") (name "Net-(D8-PadK)") (class "Default")
      (node (ref "D8") (pin "K") (pinfunction "K_K") (pintype "passive"))
      (node (ref "R14") (pin "1") (pinfunction "1_1") (pintype "passive"))
    )
    (net (code "66") (name "Net-(D9-PadK)") (class "Default")
      (node (ref "D9") (pin "K") (pinfunction "K_K") (pintype "passive"))
      (node (ref "R21") (pin "2") (pinfunction "2_2") (pintype "passive"))
    )
    (net (code "67") (name "Net-(D10-PadK)") (class "Default")
      (node (ref "D10") (pin "K") (pinfunction "K_K") (pintype "passive"))
      (node (ref "R29") (pin "2") (pinfunction "2_2") (pintype "passive"))
    )
    (net (code "68") (name "Net-(D11-K)") (class "Default")
      (node (ref "D11") (pin "2") (pinfunction "K_2") (pintype "passive"))
      (node (ref "JK1") (pin "2") (pinfunction "2_2") (pintype "passive"))
      (node (ref "Q6") (pin "3") (pinfunction "C_3") (pintype "passive"))
    )
    (net (code "69") (name "Net-(D12-K)") (class "Default")
      (node (ref "D12") (pin "2") (pinfunction "K_2") (pintype "passive"))
      (node (ref "JK2") (pin "2") (pinfunction "2_2") (pintype "passive"))
      (node (ref "Q7") (pin "3") (pinfunction "C_3") (pintype "passive"))
    )
    (net (code "70") (name "Net-(IC2-V3)") (class "Default")
      (node (ref "C15") (pin "2") (pinfunction "2_2") (pintype "passive"))
      (node (ref "IC2") (pin "4") (pinfunction "V3_4") (pintype "passive"))
    )
    (net (code "71") (name "Net-(IC2-XI)") (class "Default")
      (node (ref "C19") (pin "1") (pinfunction "1_1") (pintype "passive"))
      (node (ref "IC2") (pin "7") (pinfunction "XI_7") (pintype "passive"))
      (node (ref "Y2") (pin "1") (pinfunction "1_1") (pintype "passive"))
    )
    (net (code "72") (name "Net-(IC2-XO)") (class "Default")
      (node (ref "C18") (pin "1") (pinfunction "1_1") (pintype "passive"))
      (node (ref "IC2") (pin "8") (pinfunction "XO_8") (pintype "passive"))
      (node (ref "Y2") (pin "2") (pinfunction "2_2") (pintype "passive"))
    )
    (net (code "73") (name "Net-(J1-A)") (class "Default")
      (node (ref "J1") (pin "1") (pinfunction "A_1") (pintype "passive"))
      (node (ref "R5") (pin "2") (pinfunction "2_2") (pintype "passive"))
    )
    (net (code "74") (name "Net-(Q1-G)") (class "Default")
      (node (ref "Q1") (pin "3") (pinfunction "G_3") (pintype "passive"))
      (node (ref "R9") (pin "2") (pinfunction "2_2") (pintype "passive"))
      (node (ref "U1") (pin "4") (pinfunction "4_4") (pintype "passive"))
    )
    (net (code "75") (name "Net-(Q2-B)") (class "Default")
      (node (ref "Q2") (pin "1") (pinfunction "B_1") (pintype "passive"))
      (node (ref "R16") (pin "1") (pinfunction "1_1") (pintype "passive"))
      (node (ref "R17") (pin "1") (pinfunction "1_1") (pintype "passive"))
    )
    (net (code "76") (name "Net-(Q2-E)") (class "Default")
      (node (ref "D9") (pin "A") (pinfunction "A_A") (pintype "passive"))
      (node (ref "Q2") (pin "2") (pinfunction "E_2") (pintype "passive"))
      (node (ref "R17") (pin "2") (pinfunction "2_2") (pintype "passive"))
      (node (ref "R18") (pin "2") (pinfunction "2_2") (pintype "passive"))
    )
    (net (code "77") (name "Net-(Q3-G)") (class "Default")
      (node (ref "Q3") (pin "1") (pinfunction "G_1") (pintype "passive"))
      (node (ref "R18") (pin "1") (pinfunction "1_1") (pintype "passive"))
      (node (ref "R20") (pin "1") (pinfunction "1_1") (pintype "passive"))
    )
    (net (code "78") (name "Net-(Q4-B)") (class "Default")
      (node (ref "Q4") (pin "1") (pinfunction "B_1") (pintype "passive"))
      (node (ref "R23") (pin "1") (pinfunction "1_1") (pintype "passive"))
      (node (ref "R24") (pin "1") (pinfunction "1_1") (pintype "passive"))
    )
    (net (code "79") (name "Net-(Q4-E)") (class "Default")
      (node (ref "D10") (pin "A") (pinfunction "A_A") (pintype "passive"))
      (node (ref "Q4") (pin "2") (pinfunction "E_2") (pintype "passive"))
      (node (ref "R24") (pin "2") (pinfunction "2_2") (pintype "passive"))
      (node (ref "R25") (pin "2") (pinfunction "2_2") (pintype "passive"))
    )
    (net (code "80") (name "Net-(Q5-G)") (class "Default")
      (node (ref "Q5") (pin "1") (pinfunction "G_1") (pintype "passive"))
      (node (ref "R25") (pin "1") (pinfunction "1_1") (pintype "passive"))
      (node (ref "R26") (pin "1") (pinfunction "1_1") (pintype "passive"))
    )
    (net (code "81") (name "Net-(Q6-B)") (class "Default")
      (node (ref "Q6") (pin "1") (pinfunction "B_1") (pintype "passive"))
      (node (ref "R30") (pin "2") (pinfunction "2_2") (pintype "passive"))
    )
    (net (code "82") (name "Net-(Q7-B)") (class "Default")
      (node (ref "Q7") (pin "1") (pinfunction "B_1") (pintype "passive"))
      (node (ref "R31") (pin "2") (pinfunction "2_2") (pintype "passive"))
    )
    (net (code "83") (name "Net-(R4-Pad2)") (class "Default")
      (node (ref "R4") (pin "2") (pinfunction "2_2") (pintype "passive"))
      (node (ref "U1") (pin "6") (pinfunction "6_6") (pintype "passive"))
    )
    (net (code "84") (name "Net-(U1--)") (class "Default")
      (node (ref "R7") (pin "1") (pinfunction "1_1") (pintype "passive"))
      (node (ref "U1") (pin "2") (pinfunction "-_2") (pintype "passive"))
    )
    (net (code "85") (name "Net-(U2-BOOT0)") (class "Default")
      (node (ref "R15") (pin "1") (pinfunction "1_1") (pintype "passive"))
      (node (ref "U2") (pin "44") (pinfunction "BOOT0_44") (pintype "input"))
    )
    (net (code "86") (name "Net-(U3-GPIO16)") (class "Default")
      (node (ref "R12") (pin "1") (pinfunction "1_1") (pintype "passive"))
      (node (ref "U3") (pin "5") (pinfunction "GPIO16_5") (pintype "passive"))
    )
    (net (code "87") (name "VCC5") (class "Default")
      (node (ref "*1") (pin "1") (pinfunction "5V_1") (pintype "passive"))
      (node (ref "C1") (pin "2") (pinfunction "2_2") (pintype "passive"))
      (node (ref "C2") (pin "2") (pinfunction "2_2") (pintype "passive"))
      (node (ref "D5") (pin "A") (pinfunction "A_A") (pintype "passive"))
      (node (ref "JP3") (pin "1") (pinfunction "1_1") (pintype "passive"))
      (node (ref "JP6") (pin "2") (pinfunction "2_2") (pintype "passive"))
      (node (ref "Q6") (pin "2") (pinfunction "E_2") (pintype "passive"))
      (node (ref "Q7") (pin "2") (pinfunction "E_2") (pintype "passive"))
      (node (ref "R27") (pin "2") (pinfunction "2_2") (pintype "passive"))
      (node (ref "R28") (pin "2") (pinfunction "2_2") (pintype "passive"))
      (node (ref "SW1") (pin "1") (pinfunction "1_1") (pintype "passive"))
      (node (ref "SW1") (pin "3") (pinfunction "3_3") (pintype "passive"))
      (node (ref "V1") (pin "3") (pinfunction "VOUT_3") (pintype "passive"))
      (node (ref "V2") (pin "3") (pinfunction "Vin_3") (pintype "passive"))
    )
    (net (code "88") (name "VCC12") (class "Default")
      (node (ref "C3") (pin "2") (pinfunction "2_2") (pintype "passive"))
      (node (ref "C4") (pin "2") (pinfunction "2_2") (pintype "passive"))
      (node (ref "E1") (pin "1") (pinfunction "A_1") (pintype "passive"))
      (node (ref "JP5") (pin "1") (pinfunction "1_1") (pintype "passive"))
      (node (ref "JP5") (pin "3") (pinfunction "3_3") (pintype "passive"))
      (node (ref "JP5") (pin "5") (pinfunction "5_5") (pintype "passive"))
      (node (ref "L1") (pin "2") (pinfunction "2_2") (pintype "passive"))
      (node (ref "Q2") (pin "3") (pinfunction "C_3") (pintype "passive"))
      (node (ref "Q4") (pin "3") (pinfunction "C_3") (pintype "passive"))
      (node (ref "V1") (pin "1") (pinfunction "VIN_1") (pintype "passive"))
    )
    (net (code "89") (name "unconnected-(IC2-CTS#-Pad9)") (class "Default")
      (node (ref "IC2") (pin "9") (pinfunction "CTS#_9") (pintype "passive"))
    )
    (net (code "90") (name "unconnected-(IC2-DCD#-Pad12)") (class "Default")
      (node (ref "IC2") (pin "12") (pinfunction "DCD#_12") (pintype "passive"))
    )
    (net (code "91") (name "unconnected-(IC2-DSR#-Pad10)") (class "Default")
      (node (ref "IC2") (pin "10") (pinfunction "DSR#_10") (pintype "passive"))
    )
    (net (code "92") (name "unconnected-(IC2-DTR#-Pad13)") (class "Default")
      (node (ref "IC2") (pin "13") (pinfunction "DTR#_13") (pintype "passive"))
    )
    (net (code "93") (name "unconnected-(IC2-RI#-Pad11)") (class "Default")
      (node (ref "IC2") (pin "11") (pinfunction "RI#_11") (pintype "passive"))
    )
    (net (code "94") (name "unconnected-(IC2-RS232-Pad15)") (class "Default")
      (node (ref "IC2") (pin "15") (pinfunction "RS232_15") (pintype "passive"))
    )
    (net (code "95") (name "unconnected-(IC2-RTS#-Pad14)") (class "Default")
      (node (ref "IC2") (pin "14") (pinfunction "RTS#_14") (pintype "passive"))
    )
    (net (code "96") (name "unconnected-(JK1-Pad4)") (class "Default")
      (node (ref "JK1") (pin "4") (pinfunction "4_4") (pintype "passive"))
    )
    (net (code "97") (name "unconnected-(JK2-Pad4)") (class "Default")
      (node (ref "JK2") (pin "4") (pinfunction "4_4") (pintype "passive"))
    )
    (net (code "98") (name "unconnected-(U1-NC-Pad3)") (class "Default")
      (node (ref "U1") (pin "3") (pinfunction "NC_3") (pintype "passive"))
    )
    (net (code "99") (name "unconnected-(U1-Pad5)") (class "Default")
      (node (ref "U1") (pin "5") (pinfunction "5_5") (pintype "passive"))
    )
    (net (code "100") (name "unconnected-(U3-CH_PD-Pad3)") (class "Default")
      (node (ref "U3") (pin "3") (pinfunction "CH_PD_3") (pintype "passive"))
    )
    (net (code "101") (name "unconnected-(U3-GPIO0-Pad6)") (class "Default")
      (node (ref "U3") (pin "6") (pinfunction "GPIO0_6") (pintype "passive"))
    )
    (net (code "102") (name "unconnected-(U3-GPIO2-Pad4)") (class "Default")
      (node (ref "U3") (pin "4") (pinfunction "GPIO2_4") (pintype "passive"))
    )
    (net (code "103") (name "unconnected-(USB1-ID-Pad4)") (class "Default")
      (node (ref "USB1") (pin "4") (pinfunction "ID_4") (pintype "passive"))
    )
  )
)
